# RCV420_RevA.net
KiCad netlist of a schematic drawn in EAGLE
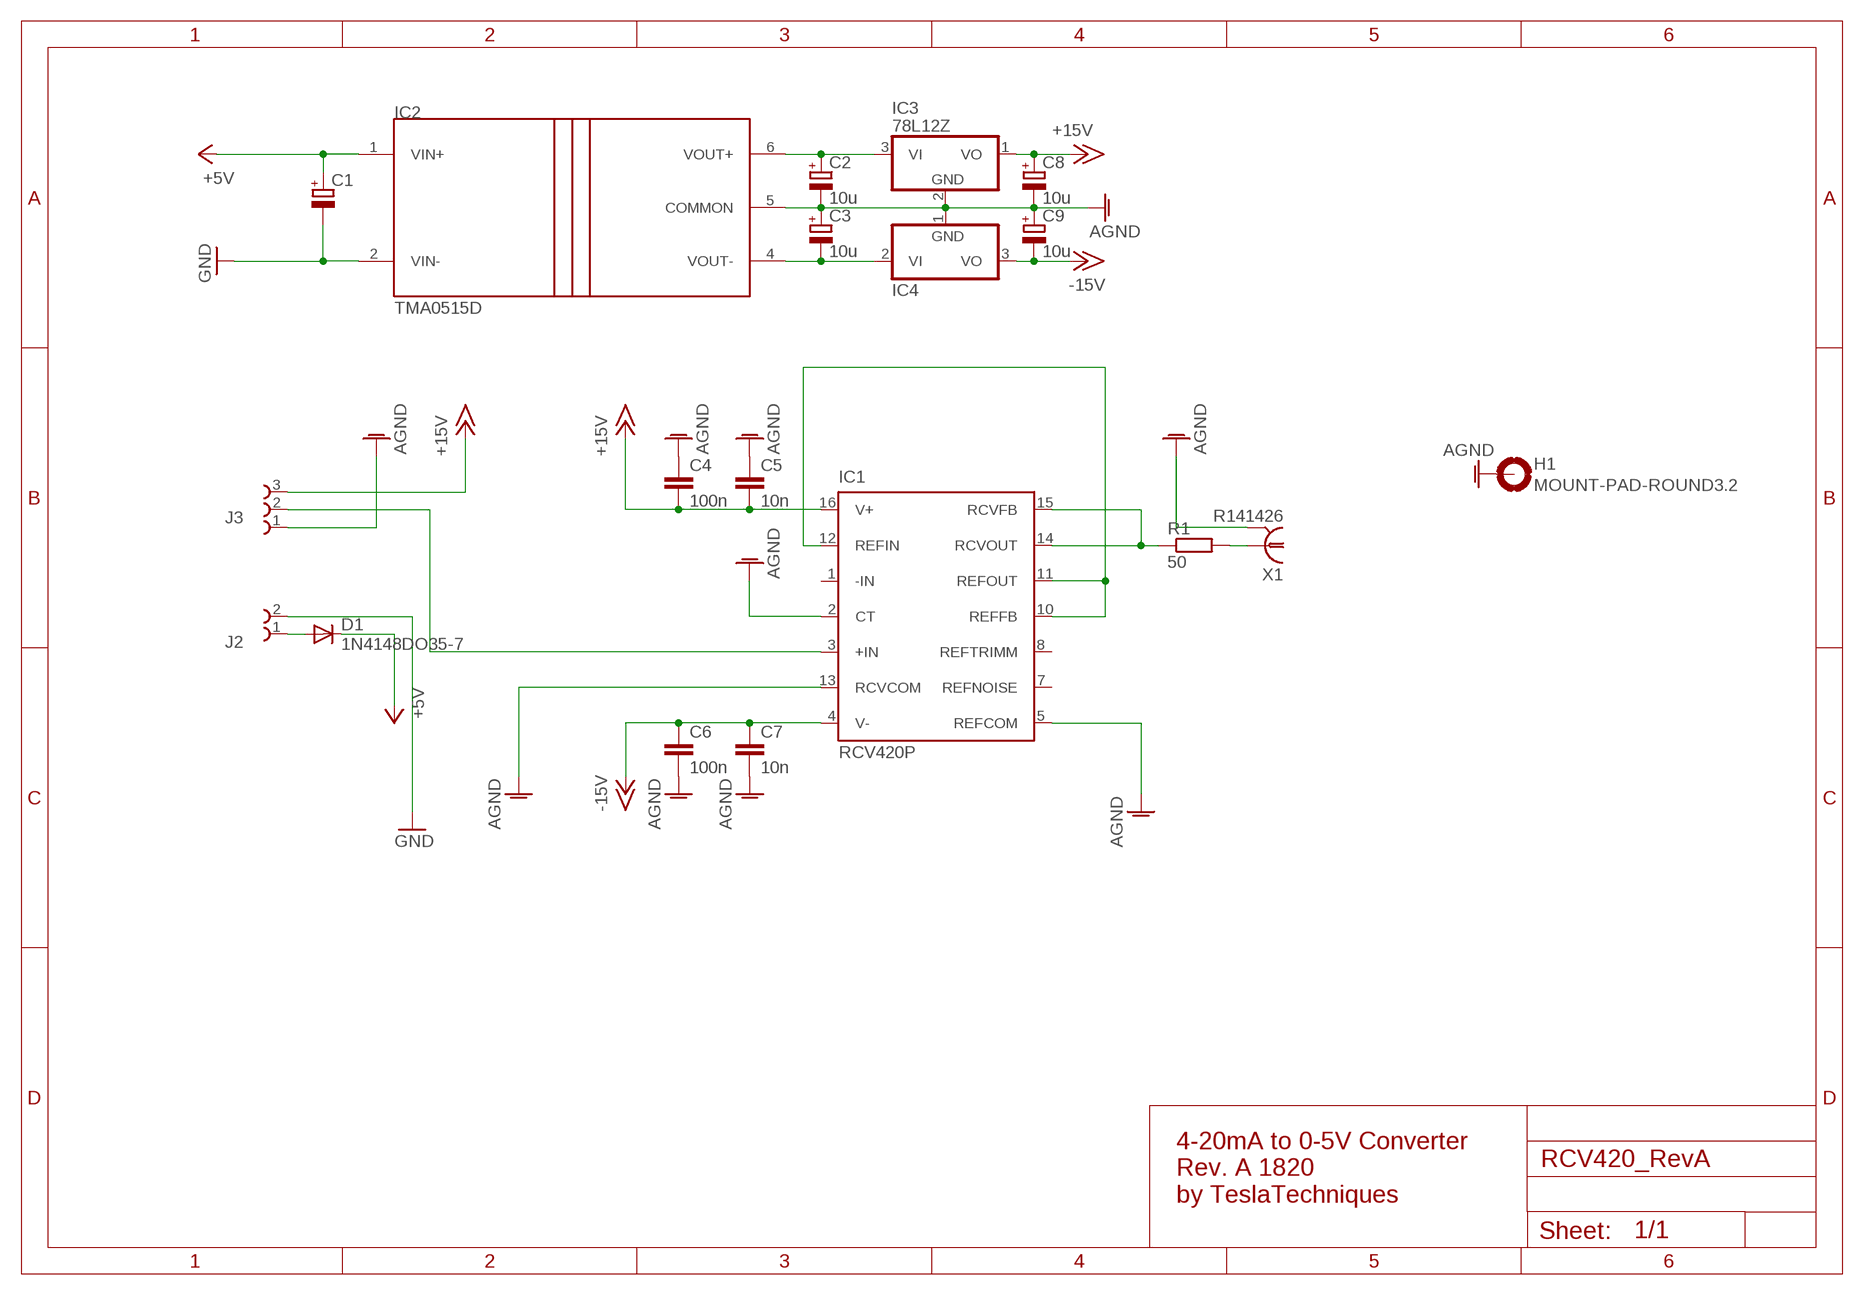
[diagram p0: schematic, sheet 1]

(export (version "E")
  (design (tool "Eeschema 10.0.6"))
  (components
    (comp (ref "C1")
      (value "CPOL-EUE2.5-5")
      (footprint "eagle-import:E2,5-5")
      (libsource (lib "eagle-import") (part "CPOL-EUE2.5-5"))
    )
    (comp (ref "C2")
      (value "10u")
      (footprint "eagle-import:E2,5-5")
      (libsource (lib "eagle-import") (part "CPOL-EUE2.5-5"))
    )
    (comp (ref "C3")
      (value "10u")
      (footprint "eagle-import:E2,5-5")
      (libsource (lib "eagle-import") (part "CPOL-EUE2.5-5"))
    )
    (comp (ref "C4")
      (value "100n")
      (footprint "eagle-import:C025-025X050")
      (libsource (lib "eagle-import") (part "C-EU025-025X050"))
    )
    (comp (ref "C5")
      (value "10n")
      (footprint "eagle-import:C025-025X050")
      (libsource (lib "eagle-import") (part "C-EU025-025X050"))
    )
    (comp (ref "C6")
      (value "100n")
      (footprint "eagle-import:C025-025X050")
      (libsource (lib "eagle-import") (part "C-EU025-025X050"))
    )
    (comp (ref "C7")
      (value "10n")
      (footprint "eagle-import:C025-025X050")
      (libsource (lib "eagle-import") (part "C-EU025-025X050"))
    )
    (comp (ref "C8")
      (value "10u")
      (footprint "eagle-import:E2,5-5")
      (libsource (lib "eagle-import") (part "CPOL-EUE2.5-5"))
    )
    (comp (ref "C9")
      (value "10u")
      (footprint "eagle-import:E2,5-5")
      (libsource (lib "eagle-import") (part "CPOL-EUE2.5-5"))
    )
    (comp (ref "D1")
      (value "1N4148DO35-7")
      (footprint "eagle-import:DO35-7")
      (libsource (lib "eagle-import") (part "1N4148DO35-7"))
    )
    (comp (ref "H1")
      (value "MOUNT-PAD-ROUND3.2")
      (footprint "eagle-import:3,2-PAD")
      (libsource (lib "eagle-import") (part "MOUNT-PAD-ROUND3.2"))
    )
    (comp (ref "IC1")
      (value "RCV420P")
      (footprint "eagle-import:DIL16")
      (fields (field (name "MF") "TEXAS INSTRUMENTS") (field (name "MPN") "RCV420JP"))
      (libsource (lib "eagle-import") (part "RCV420P"))
    )
    (comp (ref "IC2")
      (value "TMA0515D")
      (footprint "eagle-import:SIP7")
      (libsource (lib "eagle-import") (part "TMA0515D"))
    )
    (comp (ref "IC3")
      (value "78L12Z")
      (footprint "eagle-import:TO92")
      (libsource (lib "eagle-import") (part "78ZL12"))
    )
    (comp (ref "IC4")
      (value "7912L")
      (footprint "eagle-import:TO92")
      (libsource (lib "eagle-import") (part "79L12"))
    )
    (comp (ref "J2")
      (value "691111710002")
      (footprint "eagle-import:691111710002")
      (libsource (lib "eagle-import") (part "691111710002"))
    )
    (comp (ref "J3")
      (value "691111710003")
      (footprint "eagle-import:691111710003")
      (libsource (lib "eagle-import") (part "691111710003"))
    )
    (comp (ref "R1")
      (value "50")
      (footprint "eagle-import:0411_12")
      (libsource (lib "eagle-import") (part "R-EU_0411/12"))
    )
    (comp (ref "X1")
      (value "R141426")
      (footprint "eagle-import:R141426")
      (fields (field (name "MF") "FARNELL") (field (name "MPN") "R141426161"))
      (libsource (lib "eagle-import") (part "R141426"))
    )
  )
  (nets
    (net (code "1") (name "+5V") (class "Default")
      (node (ref "C1") (pin "+") (pinfunction "+_+") (pintype "passive"))
      (node (ref "D1") (pin "C") (pinfunction "C_C") (pintype "passive"))
      (node (ref "IC2") (pin "1") (pinfunction "VIN+_1") (pintype "bidirectional"))
    )
    (net (code "2") (name "+15V") (class "Default")
      (node (ref "C4") (pin "2") (pinfunction "2_2") (pintype "passive"))
      (node (ref "C5") (pin "2") (pinfunction "2_2") (pintype "passive"))
      (node (ref "C8") (pin "+") (pinfunction "+_+") (pintype "passive"))
      (node (ref "IC1") (pin "16") (pinfunction "V+_16") (pintype "input"))
      (node (ref "IC3") (pin "1") (pinfunction "VO_1") (pintype "passive"))
      (node (ref "J3") (pin "3") (pinfunction "3_3") (pintype "passive"))
    )
    (net (code "3") (name "-15V") (class "Default")
      (node (ref "C6") (pin "1") (pinfunction "1_1") (pintype "passive"))
      (node (ref "C7") (pin "1") (pinfunction "1_1") (pintype "passive"))
      (node (ref "C9") (pin "-") (pinfunction "-_-") (pintype "passive"))
      (node (ref "IC1") (pin "4") (pinfunction "V-_4") (pintype "input"))
      (node (ref "IC4") (pin "3") (pinfunction "VO_3") (pintype "passive"))
    )
    (net (code "4") (name "AGND") (class "Default")
      (node (ref "C2") (pin "-") (pinfunction "-_-") (pintype "passive"))
      (node (ref "C3") (pin "+") (pinfunction "+_+") (pintype "passive"))
      (node (ref "C4") (pin "1") (pinfunction "1_1") (pintype "passive"))
      (node (ref "C5") (pin "1") (pinfunction "1_1") (pintype "passive"))
      (node (ref "C6") (pin "2") (pinfunction "2_2") (pintype "passive"))
      (node (ref "C7") (pin "2") (pinfunction "2_2") (pintype "passive"))
      (node (ref "C8") (pin "-") (pinfunction "-_-") (pintype "passive"))
      (node (ref "C9") (pin "+") (pinfunction "+_+") (pintype "passive"))
      (node (ref "H1") (pin "B3,2") (pinfunction "MOUNT_B3,2") (pintype "passive"))
      (node (ref "IC1") (pin "13") (pinfunction "RCVCOM_13") (pintype "input"))
      (node (ref "IC1") (pin "2") (pinfunction "CT_2") (pintype "input"))
      (node (ref "IC1") (pin "5") (pinfunction "REFCOM_5") (pintype "input"))
      (node (ref "IC2") (pin "5") (pinfunction "COMMON_5") (pintype "bidirectional"))
      (node (ref "IC3") (pin "2") (pinfunction "GND_2") (pintype "passive"))
      (node (ref "IC4") (pin "1") (pinfunction "GND_1") (pintype "passive"))
      (node (ref "J3") (pin "1") (pinfunction "1_1") (pintype "passive"))
      (node (ref "X1") (pin "2") (pinfunction "2_2") (pintype "passive"))
      (node (ref "X1") (pin "3") (pinfunction "2_3") (pintype "passive"))
      (node (ref "X1") (pin "4") (pinfunction "2_4") (pintype "passive"))
      (node (ref "X1") (pin "5") (pinfunction "2_5") (pintype "passive"))
    )
    (net (code "5") (name "GND") (class "Default")
      (node (ref "C1") (pin "-") (pinfunction "-_-") (pintype "passive"))
      (node (ref "IC2") (pin "2") (pinfunction "VIN-_2") (pintype "bidirectional"))
      (node (ref "J2") (pin "2") (pinfunction "2_2") (pintype "passive"))
    )
    (net (code "6") (name "Net-(D1-PadA)") (class "Default")
      (node (ref "D1") (pin "A") (pinfunction "A_A") (pintype "passive"))
      (node (ref "J2") (pin "1") (pinfunction "1_1") (pintype "passive"))
    )
    (net (code "7") (name "Net-(IC1-+IN)") (class "Default")
      (node (ref "IC1") (pin "3") (pinfunction "+IN_3") (pintype "input"))
      (node (ref "J3") (pin "2") (pinfunction "2_2") (pintype "passive"))
    )
    (net (code "8") (name "Net-(IC1-RCVFB)") (class "Default")
      (node (ref "IC1") (pin "14") (pinfunction "RCVOUT_14") (pintype "output"))
      (node (ref "IC1") (pin "15") (pinfunction "RCVFB_15") (pintype "input"))
      (node (ref "R1") (pin "1") (pinfunction "1_1") (pintype "passive"))
    )
    (net (code "9") (name "Net-(IC1-REFFB)") (class "Default")
      (node (ref "IC1") (pin "10") (pinfunction "REFFB_10") (pintype "input"))
      (node (ref "IC1") (pin "11") (pinfunction "REFOUT_11") (pintype "output"))
      (node (ref "IC1") (pin "12") (pinfunction "REFIN_12") (pintype "input"))
    )
    (net (code "10") (name "Net-(IC2-VOUT+)") (class "Default")
      (node (ref "C2") (pin "+") (pinfunction "+_+") (pintype "passive"))
      (node (ref "IC2") (pin "6") (pinfunction "VOUT+_6") (pintype "bidirectional"))
      (node (ref "IC3") (pin "3") (pinfunction "VI_3") (pintype "input"))
    )
    (net (code "11") (name "Net-(IC2-VOUT-)") (class "Default")
      (node (ref "C3") (pin "-") (pinfunction "-_-") (pintype "passive"))
      (node (ref "IC2") (pin "4") (pinfunction "VOUT-_4") (pintype "bidirectional"))
      (node (ref "IC4") (pin "2") (pinfunction "VI_2") (pintype "input"))
    )
    (net (code "12") (name "Net-(R1-Pad2)") (class "Default")
      (node (ref "R1") (pin "2") (pinfunction "2_2") (pintype "passive"))
      (node (ref "X1") (pin "1") (pinfunction "1_1") (pintype "passive"))
    )
    (net (code "13") (name "unconnected-(IC1--IN-Pad1)") (class "Default")
      (node (ref "IC1") (pin "1") (pinfunction "-IN_1") (pintype "input"))
    )
    (net (code "14") (name "unconnected-(IC1-REFNOISE-Pad7)") (class "Default")
      (node (ref "IC1") (pin "7") (pinfunction "REFNOISE_7") (pintype "input"))
    )
    (net (code "15") (name "unconnected-(IC1-REFTRIMM-Pad8)") (class "Default")
      (node (ref "IC1") (pin "8") (pinfunction "REFTRIMM_8") (pintype "input"))
    )
  )
)
